# top_schem_rev1.net
KiCad netlist of a schematic drawn in Altium Designer
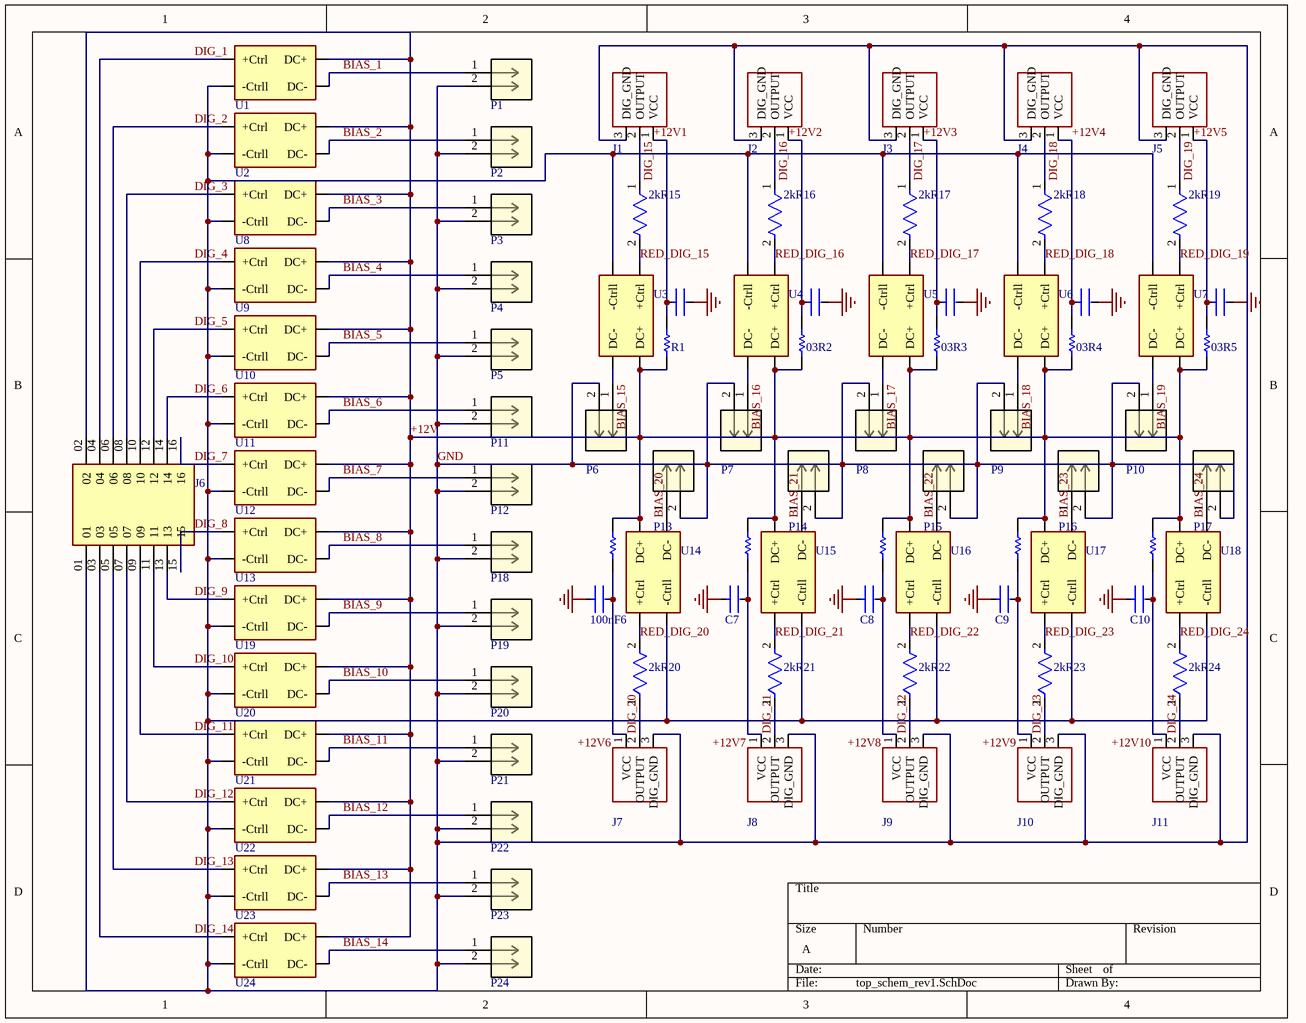
[diagram p0: top_schem_rev1.SchDoc]

(export (version "E")
  (design (tool "Eeschema 10.0.6"))
  (components
    (comp (ref "2kR15")
      (value "CRCW06031K80FKEA")
      (footprint "2kOhm")
      (description "Res Thick Film 0603 1.8K Ohm 1% 1/10W ±100ppm/°C Molded SMD Paper T/R")
      (fields (field (name "MANUFACTURER") "Vishay") (field (name "TOLERANCE") "1%"))
      (libsource (lib "ps_schlib") (part "CRCW06031K80FKEA"))
    )
    (comp (ref "2kR16")
      (value "CRCW06031K80FKEA")
      (footprint "2kOhm")
      (description "Res Thick Film 0603 1.8K Ohm 1% 1/10W ±100ppm/°C Molded SMD Paper T/R")
      (fields (field (name "MANUFACTURER") "Vishay") (field (name "TOLERANCE") "1%"))
      (libsource (lib "ps_schlib") (part "CRCW06031K80FKEA"))
    )
    (comp (ref "2kR17")
      (value "CRCW06031K80FKEA")
      (footprint "2kOhm")
      (description "Res Thick Film 0603 1.8K Ohm 1% 1/10W ±100ppm/°C Molded SMD Paper T/R")
      (fields (field (name "MANUFACTURER") "Vishay") (field (name "TOLERANCE") "1%"))
      (libsource (lib "ps_schlib") (part "CRCW06031K80FKEA"))
    )
    (comp (ref "2kR18")
      (value "CRCW06031K80FKEA")
      (footprint "2kOhm")
      (description "Res Thick Film 0603 1.8K Ohm 1% 1/10W ±100ppm/°C Molded SMD Paper T/R")
      (fields (field (name "MANUFACTURER") "Vishay") (field (name "TOLERANCE") "1%"))
      (libsource (lib "ps_schlib") (part "CRCW06031K80FKEA"))
    )
    (comp (ref "2kR19")
      (value "CRCW06031K80FKEA")
      (footprint "2kOhm")
      (description "Res Thick Film 0603 1.8K Ohm 1% 1/10W ±100ppm/°C Molded SMD Paper T/R")
      (fields (field (name "MANUFACTURER") "Vishay") (field (name "TOLERANCE") "1%"))
      (libsource (lib "ps_schlib") (part "CRCW06031K80FKEA"))
    )
    (comp (ref "2kR20")
      (value "CRCW06031K80FKEA")
      (footprint "2kOhm")
      (description "Res Thick Film 0603 1.8K Ohm 1% 1/10W ±100ppm/°C Molded SMD Paper T/R")
      (fields (field (name "MANUFACTURER") "Vishay") (field (name "TOLERANCE") "1%"))
      (libsource (lib "ps_schlib") (part "CRCW06031K80FKEA"))
    )
    (comp (ref "2kR21")
      (value "CRCW06031K80FKEA")
      (footprint "2kOhm")
      (description "Res Thick Film 0603 1.8K Ohm 1% 1/10W ±100ppm/°C Molded SMD Paper T/R")
      (fields (field (name "MANUFACTURER") "Vishay") (field (name "TOLERANCE") "1%"))
      (libsource (lib "ps_schlib") (part "CRCW06031K80FKEA"))
    )
    (comp (ref "2kR22")
      (value "CRCW06031K80FKEA")
      (footprint "2kOhm")
      (description "Res Thick Film 0603 1.8K Ohm 1% 1/10W ±100ppm/°C Molded SMD Paper T/R")
      (fields (field (name "MANUFACTURER") "Vishay") (field (name "TOLERANCE") "1%"))
      (libsource (lib "ps_schlib") (part "CRCW06031K80FKEA"))
    )
    (comp (ref "2kR23")
      (value "CRCW06031K80FKEA")
      (footprint "2kOhm")
      (description "Res Thick Film 0603 1.8K Ohm 1% 1/10W ±100ppm/°C Molded SMD Paper T/R")
      (fields (field (name "MANUFACTURER") "Vishay") (field (name "TOLERANCE") "1%"))
      (libsource (lib "ps_schlib") (part "CRCW06031K80FKEA"))
    )
    (comp (ref "2kR24")
      (value "CRCW06031K80FKEA")
      (footprint "2kOhm")
      (description "Res Thick Film 0603 1.8K Ohm 1% 1/10W ±100ppm/°C Molded SMD Paper T/R")
      (fields (field (name "MANUFACTURER") "Vishay") (field (name "TOLERANCE") "1%"))
      (libsource (lib "ps_schlib") (part "CRCW06031K80FKEA"))
    )
    (comp (ref "03R2")
      (value "ERJ-2BQJR30X")
      (footprint "03 Ohm")
      (description "RES 0.3 OHM 5% 1/6W 0402")
      (fields (field (name "MANUFACTURER") "Panasonic") (field (name "TOLERANCE") "5%"))
      (libsource (lib "ps_schlib") (part "ERJ-2BQJR30X"))
    )
    (comp (ref "03R3")
      (value "ERJ-2BQJR30X")
      (footprint "03 Ohm")
      (description "RES 0.3 OHM 5% 1/6W 0402")
      (fields (field (name "MANUFACTURER") "Panasonic") (field (name "TOLERANCE") "5%"))
      (libsource (lib "ps_schlib") (part "ERJ-2BQJR30X"))
    )
    (comp (ref "03R4")
      (value "ERJ-2BQJR30X")
      (footprint "03 Ohm")
      (description "RES 0.3 OHM 5% 1/6W 0402")
      (fields (field (name "MANUFACTURER") "Panasonic") (field (name "TOLERANCE") "5%"))
      (libsource (lib "ps_schlib") (part "ERJ-2BQJR30X"))
    )
    (comp (ref "03R5")
      (value "ERJ-2BQJR30X")
      (footprint "03 Ohm")
      (description "RES 0.3 OHM 5% 1/6W 0402")
      (fields (field (name "MANUFACTURER") "Panasonic") (field (name "TOLERANCE") "5%"))
      (libsource (lib "ps_schlib") (part "ERJ-2BQJR30X"))
    )
    (comp (ref "03R7")
      (value "ERJ-2BQJR30X")
      (footprint "03 Ohm")
      (description "RES 0.3 OHM 5% 1/6W 0402")
      (fields (field (name "MANUFACTURER") "Panasonic") (field (name "TOLERANCE") "5%"))
      (libsource (lib "ps_schlib") (part "ERJ-2BQJR30X"))
    )
    (comp (ref "03R8")
      (value "ERJ-2BQJR30X")
      (footprint "03 Ohm")
      (description "RES 0.3 OHM 5% 1/6W 0402")
      (fields (field (name "MANUFACTURER") "Panasonic") (field (name "TOLERANCE") "5%"))
      (libsource (lib "ps_schlib") (part "ERJ-2BQJR30X"))
    )
    (comp (ref "03R9")
      (value "ERJ-2BQJR30X")
      (footprint "03 Ohm")
      (description "RES 0.3 OHM 5% 1/6W 0402")
      (fields (field (name "MANUFACTURER") "Panasonic") (field (name "TOLERANCE") "5%"))
      (libsource (lib "ps_schlib") (part "ERJ-2BQJR30X"))
    )
    (comp (ref "03R10")
      (value "ERJ-2BQJR30X")
      (footprint "03 Ohm")
      (description "RES 0.3 OHM 5% 1/6W 0402")
      (fields (field (name "MANUFACTURER") "Panasonic") (field (name "TOLERANCE") "5%"))
      (libsource (lib "ps_schlib") (part "ERJ-2BQJR30X"))
    )
    (comp (ref "100nF1")
      (value "C0805C104K5RACTU")
      (footprint "100nF")
      (description "Cap Ceramic 0.1uF 50V X7R 10% SMD 2.0 x 1.2 mm 125 C Paper T/R")
      (fields (field (name "MANUFACTURER") "KEMET") (field (name "TOLERANCE") "10%"))
      (libsource (lib "ps_schlib") (part "C0805C104K5RACTU"))
    )
    (comp (ref "100nF6")
      (value "C0805C104K5RACTU")
      (footprint "100nF")
      (description "Cap Ceramic 0.1uF 50V X7R 10% SMD 2.0 x 1.2 mm 125 C Paper T/R")
      (fields (field (name "MANUFACTURER") "KEMET") (field (name "TOLERANCE") "10%"))
      (libsource (lib "ps_schlib") (part "C0805C104K5RACTU"))
    )
    (comp (ref "C2")
      (value "C0805C104K5RACTU")
      (footprint "100nF")
      (description "Cap Ceramic 0.1uF 50V X7R 10% SMD 2.0 x 1.2 mm 125 C Paper T/R")
      (fields (field (name "MANUFACTURER") "KEMET") (field (name "TOLERANCE") "10%"))
      (libsource (lib "ps_schlib") (part "C0805C104K5RACTU"))
    )
    (comp (ref "C3")
      (value "C0805C104K5RACTU")
      (footprint "100nF")
      (description "Cap Ceramic 0.1uF 50V X7R 10% SMD 2.0 x 1.2 mm 125 C Paper T/R")
      (fields (field (name "MANUFACTURER") "KEMET") (field (name "TOLERANCE") "10%"))
      (libsource (lib "ps_schlib") (part "C0805C104K5RACTU"))
    )
    (comp (ref "C4")
      (value "C0805C104K5RACTU")
      (footprint "100nF")
      (description "Cap Ceramic 0.1uF 50V X7R 10% SMD 2.0 x 1.2 mm 125 C Paper T/R")
      (fields (field (name "MANUFACTURER") "KEMET") (field (name "TOLERANCE") "10%"))
      (libsource (lib "ps_schlib") (part "C0805C104K5RACTU"))
    )
    (comp (ref "C5")
      (value "C0805C104K5RACTU")
      (footprint "100nF")
      (description "Cap Ceramic 0.1uF 50V X7R 10% SMD 2.0 x 1.2 mm 125 C Paper T/R")
      (fields (field (name "MANUFACTURER") "KEMET") (field (name "TOLERANCE") "10%"))
      (libsource (lib "ps_schlib") (part "C0805C104K5RACTU"))
    )
    (comp (ref "C7")
      (value "C0805C104K5RACTU")
      (footprint "100nF")
      (description "Cap Ceramic 0.1uF 50V X7R 10% SMD 2.0 x 1.2 mm 125 C Paper T/R")
      (fields (field (name "MANUFACTURER") "KEMET") (field (name "TOLERANCE") "10%"))
      (libsource (lib "ps_schlib") (part "C0805C104K5RACTU"))
    )
    (comp (ref "C8")
      (value "C0805C104K5RACTU")
      (footprint "100nF")
      (description "Cap Ceramic 0.1uF 50V X7R 10% SMD 2.0 x 1.2 mm 125 C Paper T/R")
      (fields (field (name "MANUFACTURER") "KEMET") (field (name "TOLERANCE") "10%"))
      (libsource (lib "ps_schlib") (part "C0805C104K5RACTU"))
    )
    (comp (ref "C9")
      (value "C0805C104K5RACTU")
      (footprint "100nF")
      (description "Cap Ceramic 0.1uF 50V X7R 10% SMD 2.0 x 1.2 mm 125 C Paper T/R")
      (fields (field (name "MANUFACTURER") "KEMET") (field (name "TOLERANCE") "10%"))
      (libsource (lib "ps_schlib") (part "C0805C104K5RACTU"))
    )
    (comp (ref "C10")
      (value "C0805C104K5RACTU")
      (footprint "100nF")
      (description "Cap Ceramic 0.1uF 50V X7R 10% SMD 2.0 x 1.2 mm 125 C Paper T/R")
      (fields (field (name "MANUFACTURER") "KEMET") (field (name "TOLERANCE") "10%"))
      (libsource (lib "ps_schlib") (part "C0805C104K5RACTU"))
    )
    (comp (ref "J1")
      (value "IF-D95T")
      (footprint "IF-D95")
      (description "DETECTOR PHOTOLOGIC TTL/CMOS")
      (fields (field (name "MANUFACTURER") "Industrial Fiber Optics"))
      (libsource (lib "ps_schlib") (part "IF-D95T"))
    )
    (comp (ref "J2")
      (value "IF-D95T")
      (footprint "IF-D95")
      (description "DETECTOR PHOTOLOGIC TTL/CMOS")
      (fields (field (name "MANUFACTURER") "Industrial Fiber Optics"))
      (libsource (lib "ps_schlib") (part "IF-D95T"))
    )
    (comp (ref "J3")
      (value "IF-D95T")
      (footprint "IF-D95")
      (description "DETECTOR PHOTOLOGIC TTL/CMOS")
      (fields (field (name "MANUFACTURER") "Industrial Fiber Optics"))
      (libsource (lib "ps_schlib") (part "IF-D95T"))
    )
    (comp (ref "J4")
      (value "IF-D95T")
      (footprint "IF-D95")
      (description "DETECTOR PHOTOLOGIC TTL/CMOS")
      (fields (field (name "MANUFACTURER") "Industrial Fiber Optics"))
      (libsource (lib "ps_schlib") (part "IF-D95T"))
    )
    (comp (ref "J5")
      (value "IF-D95T")
      (footprint "IF-D95")
      (description "DETECTOR PHOTOLOGIC TTL/CMOS")
      (fields (field (name "MANUFACTURER") "Industrial Fiber Optics"))
      (libsource (lib "ps_schlib") (part "IF-D95T"))
    )
    (comp (ref "J6")
      (value "SSM-108-X-DV")
      (footprint "16 pin header")
      (libsource (lib "ps_schlib") (part "SSM-108-X-DV"))
    )
    (comp (ref "J7")
      (value "IF-D95T")
      (footprint "IF-D95")
      (description "DETECTOR PHOTOLOGIC TTL/CMOS")
      (fields (field (name "MANUFACTURER") "Industrial Fiber Optics"))
      (libsource (lib "ps_schlib") (part "IF-D95T"))
    )
    (comp (ref "J8")
      (value "IF-D95T")
      (footprint "IF-D95")
      (description "DETECTOR PHOTOLOGIC TTL/CMOS")
      (fields (field (name "MANUFACTURER") "Industrial Fiber Optics"))
      (libsource (lib "ps_schlib") (part "IF-D95T"))
    )
    (comp (ref "J9")
      (value "IF-D95T")
      (footprint "IF-D95")
      (description "DETECTOR PHOTOLOGIC TTL/CMOS")
      (fields (field (name "MANUFACTURER") "Industrial Fiber Optics"))
      (libsource (lib "ps_schlib") (part "IF-D95T"))
    )
    (comp (ref "J10")
      (value "IF-D95T")
      (footprint "IF-D95")
      (description "DETECTOR PHOTOLOGIC TTL/CMOS")
      (fields (field (name "MANUFACTURER") "Industrial Fiber Optics"))
      (libsource (lib "ps_schlib") (part "IF-D95T"))
    )
    (comp (ref "J11")
      (value "IF-D95T")
      (footprint "IF-D95")
      (description "DETECTOR PHOTOLOGIC TTL/CMOS")
      (fields (field (name "MANUFACTURER") "Industrial Fiber Optics"))
      (libsource (lib "ps_schlib") (part "IF-D95T"))
    )
    (comp (ref "P1")
      (value "1054311102")
      (footprint "CONN_1054311102_MOL")
      (fields (field (name "MANUFACTURER") "Molex"))
      (libsource (lib "") (part "1054311102_1"))
    )
    (comp (ref "P2")
      (value "1054311102")
      (footprint "CONN_1054311102_MOL")
      (fields (field (name "MANUFACTURER") "Molex"))
      (libsource (lib "") (part "1054311102_1"))
    )
    (comp (ref "P3")
      (value "1054311102")
      (footprint "CONN_1054311102_MOL")
      (fields (field (name "MANUFACTURER") "Molex"))
      (libsource (lib "") (part "1054311102_1"))
    )
    (comp (ref "P4")
      (value "1054311102")
      (footprint "CONN_1054311102_MOL")
      (fields (field (name "MANUFACTURER") "Molex"))
      (libsource (lib "") (part "1054311102_1"))
    )
    (comp (ref "P5")
      (value "1054311102")
      (footprint "CONN_1054311102_MOL")
      (fields (field (name "MANUFACTURER") "Molex"))
      (libsource (lib "") (part "1054311102_1"))
    )
    (comp (ref "P6")
      (value "1054311102")
      (footprint "CONN_1054311102_MOL")
      (fields (field (name "MANUFACTURER") "Molex"))
      (libsource (lib "ps_schlib") (part "1054311102"))
    )
    (comp (ref "P7")
      (value "1054311102")
      (footprint "CONN_1054311102_MOL")
      (fields (field (name "MANUFACTURER") "Molex"))
      (libsource (lib "ps_schlib") (part "1054311102"))
    )
    (comp (ref "P8")
      (value "1054311102")
      (footprint "CONN_1054311102_MOL")
      (fields (field (name "MANUFACTURER") "Molex"))
      (libsource (lib "ps_schlib") (part "1054311102"))
    )
    (comp (ref "P9")
      (value "1054311102")
      (footprint "CONN_1054311102_MOL")
      (fields (field (name "MANUFACTURER") "Molex"))
      (libsource (lib "ps_schlib") (part "1054311102"))
    )
    (comp (ref "P10")
      (value "1054311102")
      (footprint "CONN_1054311102_MOL")
      (fields (field (name "MANUFACTURER") "Molex"))
      (libsource (lib "ps_schlib") (part "1054311102"))
    )
    (comp (ref "P11")
      (value "1054311102")
      (footprint "CONN_1054311102_MOL")
      (fields (field (name "MANUFACTURER") "Molex"))
      (libsource (lib "") (part "1054311102_1"))
    )
    (comp (ref "P12")
      (value "1054311102")
      (footprint "CONN_1054311102_MOL")
      (fields (field (name "MANUFACTURER") "Molex"))
      (libsource (lib "") (part "1054311102_1"))
    )
    (comp (ref "P13")
      (value "1054311102")
      (footprint "CONN_1054311102_MOL")
      (fields (field (name "MANUFACTURER") "Molex"))
      (libsource (lib "") (part "1054311102_2"))
    )
    (comp (ref "P14")
      (value "1054311102")
      (footprint "CONN_1054311102_MOL")
      (fields (field (name "MANUFACTURER") "Molex"))
      (libsource (lib "") (part "1054311102_2"))
    )
    (comp (ref "P15")
      (value "1054311102")
      (footprint "CONN_1054311102_MOL")
      (fields (field (name "MANUFACTURER") "Molex"))
      (libsource (lib "") (part "1054311102_2"))
    )
    (comp (ref "P16")
      (value "1054311102")
      (footprint "CONN_1054311102_MOL")
      (fields (field (name "MANUFACTURER") "Molex"))
      (libsource (lib "") (part "1054311102_2"))
    )
    (comp (ref "P17")
      (value "1054311102")
      (footprint "CONN_1054311102_MOL")
      (fields (field (name "MANUFACTURER") "Molex"))
      (libsource (lib "") (part "1054311102_2"))
    )
    (comp (ref "P18")
      (value "1054311102")
      (footprint "CONN_1054311102_MOL")
      (fields (field (name "MANUFACTURER") "Molex"))
      (libsource (lib "") (part "1054311102_1"))
    )
    (comp (ref "P19")
      (value "1054311102")
      (footprint "CONN_1054311102_MOL")
      (fields (field (name "MANUFACTURER") "Molex"))
      (libsource (lib "") (part "1054311102_1"))
    )
    (comp (ref "P20")
      (value "1054311102")
      (footprint "CONN_1054311102_MOL")
      (fields (field (name "MANUFACTURER") "Molex"))
      (libsource (lib "") (part "1054311102_1"))
    )
    (comp (ref "P21")
      (value "1054311102")
      (footprint "CONN_1054311102_MOL")
      (fields (field (name "MANUFACTURER") "Molex"))
      (libsource (lib "") (part "1054311102_1"))
    )
    (comp (ref "P22")
      (value "1054311102")
      (footprint "CONN_1054311102_MOL")
      (fields (field (name "MANUFACTURER") "Molex"))
      (libsource (lib "") (part "1054311102_1"))
    )
    (comp (ref "P23")
      (value "1054311102")
      (footprint "CONN_1054311102_MOL")
      (fields (field (name "MANUFACTURER") "Molex"))
      (libsource (lib "") (part "1054311102_1"))
    )
    (comp (ref "P24")
      (value "1054311102")
      (footprint "CONN_1054311102_MOL")
      (fields (field (name "MANUFACTURER") "Molex"))
      (libsource (lib "") (part "1054311102_1"))
    )
    (comp (ref "R1")
      (value "ERJ-2BQJR30X")
      (footprint "03 Ohm")
      (description "RES 0.3 OHM 5% 1/6W 0402")
      (fields (field (name "MANUFACTURER") "Panasonic") (field (name "TOLERANCE") "5%"))
      (libsource (lib "ps_schlib") (part "ERJ-2BQJR30X"))
    )
    (comp (ref "R6")
      (value "ERJ-2BQJR30X")
      (footprint "03 Ohm")
      (description "RES 0.3 OHM 5% 1/6W 0402")
      (fields (field (name "MANUFACTURER") "Panasonic") (field (name "TOLERANCE") "5%"))
      (libsource (lib "ps_schlib") (part "ERJ-2BQJR30X"))
    )
    (comp (ref "U1")
      (value "Solid state relay")
      (footprint "CPC1002N")
      (libsource (lib "") (part "CPC1002N_2"))
    )
    (comp (ref "U2")
      (value "Solid state relay")
      (footprint "CPC1002N")
      (libsource (lib "") (part "CPC1002N_2"))
    )
    (comp (ref "U3")
      (value "Solid state relay")
      (footprint "CPC1002N")
      (libsource (lib "ps_schlib") (part "CPC1002N"))
    )
    (comp (ref "U4")
      (value "Solid state relay")
      (footprint "CPC1002N")
      (libsource (lib "ps_schlib") (part "CPC1002N"))
    )
    (comp (ref "U5")
      (value "Solid state relay")
      (footprint "CPC1002N")
      (libsource (lib "ps_schlib") (part "CPC1002N"))
    )
    (comp (ref "U6")
      (value "Solid state relay")
      (footprint "CPC1002N")
      (libsource (lib "ps_schlib") (part "CPC1002N"))
    )
    (comp (ref "U7")
      (value "Solid state relay")
      (footprint "CPC1002N")
      (libsource (lib "ps_schlib") (part "CPC1002N"))
    )
    (comp (ref "U8")
      (value "Solid state relay")
      (footprint "CPC1002N")
      (libsource (lib "") (part "CPC1002N_2"))
    )
    (comp (ref "U9")
      (value "Solid state relay")
      (footprint "CPC1002N")
      (libsource (lib "") (part "CPC1002N_2"))
    )
    (comp (ref "U10")
      (value "Solid state relay")
      (footprint "CPC1002N")
      (libsource (lib "") (part "CPC1002N_2"))
    )
    (comp (ref "U11")
      (value "Solid state relay")
      (footprint "CPC1002N")
      (libsource (lib "") (part "CPC1002N_2"))
    )
    (comp (ref "U12")
      (value "Solid state relay")
      (footprint "CPC1002N")
      (libsource (lib "") (part "CPC1002N_2"))
    )
    (comp (ref "U13")
      (value "Solid state relay")
      (footprint "CPC1002N")
      (libsource (lib "") (part "CPC1002N_2"))
    )
    (comp (ref "U14")
      (value "Solid state relay")
      (footprint "CPC1002N")
      (libsource (lib "") (part "CPC1002N_1"))
    )
    (comp (ref "U15")
      (value "Solid state relay")
      (footprint "CPC1002N")
      (libsource (lib "") (part "CPC1002N_1"))
    )
    (comp (ref "U16")
      (value "Solid state relay")
      (footprint "CPC1002N")
      (libsource (lib "") (part "CPC1002N_1"))
    )
    (comp (ref "U17")
      (value "Solid state relay")
      (footprint "CPC1002N")
      (libsource (lib "") (part "CPC1002N_1"))
    )
    (comp (ref "U18")
      (value "Solid state relay")
      (footprint "CPC1002N")
      (libsource (lib "") (part "CPC1002N_1"))
    )
    (comp (ref "U19")
      (value "Solid state relay")
      (footprint "CPC1002N")
      (libsource (lib "") (part "CPC1002N_2"))
    )
    (comp (ref "U20")
      (value "Solid state relay")
      (footprint "CPC1002N")
      (libsource (lib "") (part "CPC1002N_2"))
    )
    (comp (ref "U21")
      (value "Solid state relay")
      (footprint "CPC1002N")
      (libsource (lib "") (part "CPC1002N_2"))
    )
    (comp (ref "U22")
      (value "Solid state relay")
      (footprint "CPC1002N")
      (libsource (lib "") (part "CPC1002N_2"))
    )
    (comp (ref "U23")
      (value "Solid state relay")
      (footprint "CPC1002N")
      (libsource (lib "") (part "CPC1002N_2"))
    )
    (comp (ref "U24")
      (value "Solid state relay")
      (footprint "CPC1002N")
      (libsource (lib "") (part "CPC1002N_2"))
    )
  )
  (nets
    (net (code "1") (name "/+12V") (class "Default")
      (node (ref "03R10") (pin "2") (pinfunction "2_2") (pintype "passive"))
      (node (ref "03R2") (pin "1") (pinfunction "1_1") (pintype "passive"))
      (node (ref "03R3") (pin "1") (pinfunction "1_1") (pintype "passive"))
      (node (ref "03R4") (pin "1") (pinfunction "1_1") (pintype "passive"))
      (node (ref "03R5") (pin "1") (pinfunction "1_1") (pintype "passive"))
      (node (ref "03R7") (pin "2") (pinfunction "2_2") (pintype "passive"))
      (node (ref "03R8") (pin "2") (pinfunction "2_2") (pintype "passive"))
      (node (ref "03R9") (pin "2") (pinfunction "2_2") (pintype "passive"))
      (node (ref "J6") (pin "02") (pinfunction "02_02") (pintype "passive"))
      (node (ref "R1") (pin "1") (pinfunction "1_1") (pintype "passive"))
      (node (ref "R6") (pin "2") (pinfunction "2_2") (pintype "passive"))
      (node (ref "U1") (pin "4") (pinfunction "DC+_4") (pintype "passive"))
      (node (ref "U10") (pin "4") (pinfunction "DC+_4") (pintype "passive"))
      (node (ref "U11") (pin "4") (pinfunction "DC+_4") (pintype "passive"))
      (node (ref "U12") (pin "4") (pinfunction "DC+_4") (pintype "passive"))
      (node (ref "U13") (pin "4") (pinfunction "DC+_4") (pintype "passive"))
      (node (ref "U14") (pin "4") (pinfunction "DC+_4") (pintype "passive"))
      (node (ref "U15") (pin "4") (pinfunction "DC+_4") (pintype "passive"))
      (node (ref "U16") (pin "4") (pinfunction "DC+_4") (pintype "passive"))
      (node (ref "U17") (pin "4") (pinfunction "DC+_4") (pintype "passive"))
      (node (ref "U18") (pin "4") (pinfunction "DC+_4") (pintype "passive"))
      (node (ref "U19") (pin "4") (pinfunction "DC+_4") (pintype "passive"))
      (node (ref "U2") (pin "4") (pinfunction "DC+_4") (pintype "passive"))
      (node (ref "U20") (pin "4") (pinfunction "DC+_4") (pintype "passive"))
      (node (ref "U21") (pin "4") (pinfunction "DC+_4") (pintype "passive"))
      (node (ref "U22") (pin "4") (pinfunction "DC+_4") (pintype "passive"))
      (node (ref "U23") (pin "4") (pinfunction "DC+_4") (pintype "passive"))
      (node (ref "U24") (pin "4") (pinfunction "DC+_4") (pintype "passive"))
      (node (ref "U3") (pin "4") (pinfunction "DC+_4") (pintype "passive"))
      (node (ref "U4") (pin "4") (pinfunction "DC+_4") (pintype "passive"))
      (node (ref "U5") (pin "4") (pinfunction "DC+_4") (pintype "passive"))
      (node (ref "U6") (pin "4") (pinfunction "DC+_4") (pintype "passive"))
      (node (ref "U7") (pin "4") (pinfunction "DC+_4") (pintype "passive"))
      (node (ref "U8") (pin "4") (pinfunction "DC+_4") (pintype "passive"))
      (node (ref "U9") (pin "4") (pinfunction "DC+_4") (pintype "passive"))
    )
    (net (code "2") (name "/+12V1") (class "Default")
      (node (ref "100nF1") (pin "1") (pinfunction "1_1") (pintype "passive"))
      (node (ref "J1") (pin "1") (pinfunction "VCC_1") (pintype "passive"))
      (node (ref "R1") (pin "2") (pinfunction "2_2") (pintype "passive"))
    )
    (net (code "3") (name "/+12V2") (class "Default")
      (node (ref "03R2") (pin "2") (pinfunction "2_2") (pintype "passive"))
      (node (ref "C2") (pin "1") (pinfunction "1_1") (pintype "passive"))
      (node (ref "J2") (pin "1") (pinfunction "VCC_1") (pintype "passive"))
    )
    (net (code "4") (name "/+12V3") (class "Default")
      (node (ref "03R3") (pin "2") (pinfunction "2_2") (pintype "passive"))
      (node (ref "C3") (pin "1") (pinfunction "1_1") (pintype "passive"))
      (node (ref "J3") (pin "1") (pinfunction "VCC_1") (pintype "passive"))
    )
    (net (code "5") (name "/+12V4") (class "Default")
      (node (ref "03R4") (pin "2") (pinfunction "2_2") (pintype "passive"))
      (node (ref "C4") (pin "1") (pinfunction "1_1") (pintype "passive"))
      (node (ref "J4") (pin "1") (pinfunction "VCC_1") (pintype "passive"))
    )
    (net (code "6") (name "/+12V5") (class "Default")
      (node (ref "03R5") (pin "2") (pinfunction "2_2") (pintype "passive"))
      (node (ref "C5") (pin "1") (pinfunction "1_1") (pintype "passive"))
      (node (ref "J5") (pin "1") (pinfunction "VCC_1") (pintype "passive"))
    )
    (net (code "7") (name "/+12V6") (class "Default")
      (node (ref "100nF6") (pin "2") (pinfunction "2_2") (pintype "passive"))
      (node (ref "J7") (pin "1") (pinfunction "VCC_1") (pintype "passive"))
      (node (ref "R6") (pin "1") (pinfunction "1_1") (pintype "passive"))
    )
    (net (code "8") (name "/+12V7") (class "Default")
      (node (ref "03R7") (pin "1") (pinfunction "1_1") (pintype "passive"))
      (node (ref "C7") (pin "2") (pinfunction "2_2") (pintype "passive"))
      (node (ref "J8") (pin "1") (pinfunction "VCC_1") (pintype "passive"))
    )
    (net (code "9") (name "/+12V8") (class "Default")
      (node (ref "03R8") (pin "1") (pinfunction "1_1") (pintype "passive"))
      (node (ref "C8") (pin "2") (pinfunction "2_2") (pintype "passive"))
      (node (ref "J9") (pin "1") (pinfunction "VCC_1") (pintype "passive"))
    )
    (net (code "10") (name "/+12V9") (class "Default")
      (node (ref "03R9") (pin "1") (pinfunction "1_1") (pintype "passive"))
      (node (ref "C9") (pin "2") (pinfunction "2_2") (pintype "passive"))
      (node (ref "J10") (pin "1") (pinfunction "VCC_1") (pintype "passive"))
    )
    (net (code "11") (name "/+12V10") (class "Default")
      (node (ref "03R10") (pin "1") (pinfunction "1_1") (pintype "passive"))
      (node (ref "C10") (pin "2") (pinfunction "2_2") (pintype "passive"))
      (node (ref "J11") (pin "1") (pinfunction "VCC_1") (pintype "passive"))
    )
    (net (code "12") (name "/BIAS_1") (class "Default")
      (node (ref "P1") (pin "1") (pinfunction "1_1") (pintype "passive"))
      (node (ref "U1") (pin "3") (pinfunction "DC-_3") (pintype "passive"))
    )
    (net (code "13") (name "/BIAS_2") (class "Default")
      (node (ref "P2") (pin "1") (pinfunction "1_1") (pintype "passive"))
      (node (ref "U2") (pin "3") (pinfunction "DC-_3") (pintype "passive"))
    )
    (net (code "14") (name "/BIAS_3") (class "Default")
      (node (ref "P3") (pin "1") (pinfunction "1_1") (pintype "passive"))
      (node (ref "U8") (pin "3") (pinfunction "DC-_3") (pintype "passive"))
    )
    (net (code "15") (name "/BIAS_4") (class "Default")
      (node (ref "P4") (pin "1") (pinfunction "1_1") (pintype "passive"))
      (node (ref "U9") (pin "3") (pinfunction "DC-_3") (pintype "passive"))
    )
    (net (code "16") (name "/BIAS_5") (class "Default")
      (node (ref "P5") (pin "1") (pinfunction "1_1") (pintype "passive"))
      (node (ref "U10") (pin "3") (pinfunction "DC-_3") (pintype "passive"))
    )
    (net (code "17") (name "/BIAS_6") (class "Default")
      (node (ref "P11") (pin "1") (pinfunction "1_1") (pintype "passive"))
      (node (ref "U11") (pin "3") (pinfunction "DC-_3") (pintype "passive"))
    )
    (net (code "18") (name "/BIAS_7") (class "Default")
      (node (ref "P12") (pin "1") (pinfunction "1_1") (pintype "passive"))
      (node (ref "U12") (pin "3") (pinfunction "DC-_3") (pintype "passive"))
    )
    (net (code "19") (name "/BIAS_8") (class "Default")
      (node (ref "P18") (pin "1") (pinfunction "1_1") (pintype "passive"))
      (node (ref "U13") (pin "3") (pinfunction "DC-_3") (pintype "passive"))
    )
    (net (code "20") (name "/BIAS_9") (class "Default")
      (node (ref "P19") (pin "1") (pinfunction "1_1") (pintype "passive"))
      (node (ref "U19") (pin "3") (pinfunction "DC-_3") (pintype "passive"))
    )
    (net (code "21") (name "/BIAS_10") (class "Default")
      (node (ref "P20") (pin "1") (pinfunction "1_1") (pintype "passive"))
      (node (ref "U20") (pin "3") (pinfunction "DC-_3") (pintype "passive"))
    )
    (net (code "22") (name "/BIAS_11") (class "Default")
      (node (ref "P21") (pin "1") (pinfunction "1_1") (pintype "passive"))
      (node (ref "U21") (pin "3") (pinfunction "DC-_3") (pintype "passive"))
    )
    (net (code "23") (name "/BIAS_12") (class "Default")
      (node (ref "P22") (pin "1") (pinfunction "1_1") (pintype "passive"))
      (node (ref "U22") (pin "3") (pinfunction "DC-_3") (pintype "passive"))
    )
    (net (code "24") (name "/BIAS_13") (class "Default")
      (node (ref "P23") (pin "1") (pinfunction "1_1") (pintype "passive"))
      (node (ref "U23") (pin "3") (pinfunction "DC-_3") (pintype "passive"))
    )
    (net (code "25") (name "/BIAS_14") (class "Default")
      (node (ref "P24") (pin "1") (pinfunction "1_1") (pintype "passive"))
      (node (ref "U24") (pin "3") (pinfunction "DC-_3") (pintype "passive"))
    )
    (net (code "26") (name "/BIAS_15") (class "Default")
      (node (ref "P6") (pin "1") (pinfunction "1_1") (pintype "passive"))
      (node (ref "U3") (pin "3") (pinfunction "DC-_3") (pintype "passive"))
    )
    (net (code "27") (name "/BIAS_16") (class "Default")
      (node (ref "P7") (pin "1") (pinfunction "1_1") (pintype "passive"))
      (node (ref "U4") (pin "3") (pinfunction "DC-_3") (pintype "passive"))
    )
    (net (code "28") (name "/BIAS_17") (class "Default")
      (node (ref "P8") (pin "1") (pinfunction "1_1") (pintype "passive"))
      (node (ref "U5") (pin "3") (pinfunction "DC-_3") (pintype "passive"))
    )
    (net (code "29") (name "/BIAS_18") (class "Default")
      (node (ref "P9") (pin "1") (pinfunction "1_1") (pintype "passive"))
      (node (ref "U6") (pin "3") (pinfunction "DC-_3") (pintype "passive"))
    )
    (net (code "30") (name "/BIAS_19") (class "Default")
      (node (ref "P10") (pin "1") (pinfunction "1_1") (pintype "passive"))
      (node (ref "U7") (pin "3") (pinfunction "DC-_3") (pintype "passive"))
    )
    (net (code "31") (name "/BIAS_20") (class "Default")
      (node (ref "P13") (pin "1") (pinfunction "1_1") (pintype "passive"))
      (node (ref "U14") (pin "3") (pinfunction "DC-_3") (pintype "passive"))
    )
    (net (code "32") (name "/BIAS_21") (class "Default")
      (node (ref "P14") (pin "1") (pinfunction "1_1") (pintype "passive"))
      (node (ref "U15") (pin "3") (pinfunction "DC-_3") (pintype "passive"))
    )
    (net (code "33") (name "/BIAS_22") (class "Default")
      (node (ref "P15") (pin "1") (pinfunction "1_1") (pintype "passive"))
      (node (ref "U16") (pin "3") (pinfunction "DC-_3") (pintype "passive"))
    )
    (net (code "34") (name "/BIAS_23") (class "Default")
      (node (ref "P16") (pin "1") (pinfunction "1_1") (pintype "passive"))
      (node (ref "U17") (pin "3") (pinfunction "DC-_3") (pintype "passive"))
    )
    (net (code "35") (name "/BIAS_24") (class "Default")
      (node (ref "P17") (pin "1") (pinfunction "1_1") (pintype "passive"))
      (node (ref "U18") (pin "3") (pinfunction "DC-_3") (pintype "passive"))
    )
    (net (code "36") (name "/DIG_1") (class "Default")
      (node (ref "J6") (pin "04") (pinfunction "04_04") (pintype "passive"))
      (node (ref "U1") (pin "1") (pinfunction "+Ctrl_1") (pintype "passive"))
    )
    (net (code "37") (name "/DIG_2") (class "Default")
      (node (ref "J6") (pin "06") (pinfunction "06_06") (pintype "passive"))
      (node (ref "U2") (pin "1") (pinfunction "+Ctrl_1") (pintype "passive"))
    )
    (net (code "38") (name "/DIG_3") (class "Default")
      (node (ref "J6") (pin "08") (pinfunction "08_08") (pintype "passive"))
      (node (ref "U8") (pin "1") (pinfunction "+Ctrl_1") (pintype "passive"))
    )
    (net (code "39") (name "/DIG_4") (class "Default")
      (node (ref "J6") (pin "10") (pinfunction "10_10") (pintype "passive"))
      (node (ref "U9") (pin "1") (pinfunction "+Ctrl_1") (pintype "passive"))
    )
    (net (code "40") (name "/DIG_5") (class "Default")
      (node (ref "J6") (pin "12") (pinfunction "12_12") (pintype "passive"))
      (node (ref "U10") (pin "1") (pinfunction "+Ctrl_1") (pintype "passive"))
    )
    (net (code "41") (name "/DIG_6") (class "Default")
      (node (ref "J6") (pin "14") (pinfunction "14_14") (pintype "passive"))
      (node (ref "U11") (pin "1") (pinfunction "+Ctrl_1") (pintype "passive"))
    )
    (net (code "42") (name "/DIG_7") (class "Default")
      (node (ref "J6") (pin "16") (pinfunction "16_16") (pintype "passive"))
      (node (ref "U12") (pin "1") (pinfunction "+Ctrl_1") (pintype "passive"))
    )
    (net (code "43") (name "/DIG_8") (class "Default")
      (node (ref "J6") (pin "15") (pinfunction "15_15") (pintype "passive"))
      (node (ref "U13") (pin "1") (pinfunction "+Ctrl_1") (pintype "passive"))
    )
    (net (code "44") (name "/DIG_9") (class "Default")
      (node (ref "J6") (pin "13") (pinfunction "13_13") (pintype "passive"))
      (node (ref "U19") (pin "1") (pinfunction "+Ctrl_1") (pintype "passive"))
    )
    (net (code "45") (name "/DIG_10") (class "Default")
      (node (ref "J6") (pin "11") (pinfunction "11_11") (pintype "passive"))
      (node (ref "U20") (pin "1") (pinfunction "+Ctrl_1") (pintype "passive"))
    )
    (net (code "46") (name "/DIG_11") (class "Default")
      (node (ref "J6") (pin "09") (pinfunction "09_09") (pintype "passive"))
      (node (ref "U21") (pin "1") (pinfunction "+Ctrl_1") (pintype "passive"))
    )
    (net (code "47") (name "/DIG_12") (class "Default")
      (node (ref "J6") (pin "07") (pinfunction "07_07") (pintype "passive"))
      (node (ref "U22") (pin "1") (pinfunction "+Ctrl_1") (pintype "passive"))
    )
    (net (code "48") (name "/DIG_13") (class "Default")
      (node (ref "J6") (pin "05") (pinfunction "05_05") (pintype "passive"))
      (node (ref "U23") (pin "1") (pinfunction "+Ctrl_1") (pintype "passive"))
    )
    (net (code "49") (name "/DIG_14") (class "Default")
      (node (ref "J6") (pin "03") (pinfunction "03_03") (pintype "passive"))
      (node (ref "U24") (pin "1") (pinfunction "+Ctrl_1") (pintype "passive"))
    )
    (net (code "50") (name "/DIG_15") (class "Default")
      (node (ref "2kR15") (pin "1") (pinfunction "1_1") (pintype "passive"))
      (node (ref "J1") (pin "2") (pinfunction "OUTPUT_2") (pintype "passive"))
    )
    (net (code "51") (name "/DIG_16") (class "Default")
      (node (ref "2kR16") (pin "1") (pinfunction "1_1") (pintype "passive"))
      (node (ref "J2") (pin "2") (pinfunction "OUTPUT_2") (pintype "passive"))
    )
    (net (code "52") (name "/DIG_17") (class "Default")
      (node (ref "2kR17") (pin "1") (pinfunction "1_1") (pintype "passive"))
      (node (ref "J3") (pin "2") (pinfunction "OUTPUT_2") (pintype "passive"))
    )
    (net (code "53") (name "/DIG_18") (class "Default")
      (node (ref "2kR18") (pin "1") (pinfunction "1_1") (pintype "passive"))
      (node (ref "J4") (pin "2") (pinfunction "OUTPUT_2") (pintype "passive"))
    )
    (net (code "54") (name "/DIG_19") (class "Default")
      (node (ref "2kR19") (pin "1") (pinfunction "1_1") (pintype "passive"))
      (node (ref "J5") (pin "2") (pinfunction "OUTPUT_2") (pintype "passive"))
    )
    (net (code "55") (name "/DIG_20") (class "Default")
      (node (ref "2kR20") (pin "1") (pinfunction "1_1") (pintype "passive"))
      (node (ref "J7") (pin "2") (pinfunction "OUTPUT_2") (pintype "passive"))
    )
    (net (code "56") (name "/DIG_21") (class "Default")
      (node (ref "2kR21") (pin "1") (pinfunction "1_1") (pintype "passive"))
      (node (ref "J8") (pin "2") (pinfunction "OUTPUT_2") (pintype "passive"))
    )
    (net (code "57") (name "/DIG_22") (class "Default")
      (node (ref "2kR22") (pin "1") (pinfunction "1_1") (pintype "passive"))
      (node (ref "J9") (pin "2") (pinfunction "OUTPUT_2") (pintype "passive"))
    )
    (net (code "58") (name "/DIG_23") (class "Default")
      (node (ref "2kR23") (pin "1") (pinfunction "1_1") (pintype "passive"))
      (node (ref "J10") (pin "2") (pinfunction "OUTPUT_2") (pintype "passive"))
    )
    (net (code "59") (name "/DIG_24") (class "Default")
      (node (ref "2kR24") (pin "1") (pinfunction "1_1") (pintype "passive"))
      (node (ref "J11") (pin "2") (pinfunction "OUTPUT_2") (pintype "passive"))
    )
    (net (code "60") (name "/RED_DIG_15") (class "Default")
      (node (ref "2kR15") (pin "2") (pinfunction "2_2") (pintype "passive"))
      (node (ref "U3") (pin "1") (pinfunction "+Ctrl_1") (pintype "passive"))
    )
    (net (code "61") (name "/RED_DIG_16") (class "Default")
      (node (ref "2kR16") (pin "2") (pinfunction "2_2") (pintype "passive"))
      (node (ref "U4") (pin "1") (pinfunction "+Ctrl_1") (pintype "passive"))
    )
    (net (code "62") (name "/RED_DIG_17") (class "Default")
      (node (ref "2kR17") (pin "2") (pinfunction "2_2") (pintype "passive"))
      (node (ref "U5") (pin "1") (pinfunction "+Ctrl_1") (pintype "passive"))
    )
    (net (code "63") (name "/RED_DIG_18") (class "Default")
      (node (ref "2kR18") (pin "2") (pinfunction "2_2") (pintype "passive"))
      (node (ref "U6") (pin "1") (pinfunction "+Ctrl_1") (pintype "passive"))
    )
    (net (code "64") (name "/RED_DIG_19") (class "Default")
      (node (ref "2kR19") (pin "2") (pinfunction "2_2") (pintype "passive"))
      (node (ref "U7") (pin "1") (pinfunction "+Ctrl_1") (pintype "passive"))
    )
    (net (code "65") (name "/RED_DIG_20") (class "Default")
      (node (ref "2kR20") (pin "2") (pinfunction "2_2") (pintype "passive"))
      (node (ref "U14") (pin "1") (pinfunction "+Ctrl_1") (pintype "passive"))
    )
    (net (code "66") (name "/RED_DIG_21") (class "Default")
      (node (ref "2kR21") (pin "2") (pinfunction "2_2") (pintype "passive"))
      (node (ref "U15") (pin "1") (pinfunction "+Ctrl_1") (pintype "passive"))
    )
    (net (code "67") (name "/RED_DIG_22") (class "Default")
      (node (ref "2kR22") (pin "2") (pinfunction "2_2") (pintype "passive"))
      (node (ref "U16") (pin "1") (pinfunction "+Ctrl_1") (pintype "passive"))
    )
    (net (code "68") (name "/RED_DIG_23") (class "Default")
      (node (ref "2kR23") (pin "2") (pinfunction "2_2") (pintype "passive"))
      (node (ref "U17") (pin "1") (pinfunction "+Ctrl_1") (pintype "passive"))
    )
    (net (code "69") (name "/RED_DIG_24") (class "Default")
      (node (ref "2kR24") (pin "2") (pinfunction "2_2") (pintype "passive"))
      (node (ref "U18") (pin "1") (pinfunction "+Ctrl_1") (pintype "passive"))
    )
    (net (code "70") (name "GND") (class "Default")
      (node (ref "100nF1") (pin "2") (pinfunction "2_2") (pintype "passive"))
      (node (ref "100nF6") (pin "1") (pinfunction "1_1") (pintype "passive"))
      (node (ref "C10") (pin "1") (pinfunction "1_1") (pintype "passive"))
      (node (ref "C2") (pin "2") (pinfunction "2_2") (pintype "passive"))
      (node (ref "C3") (pin "2") (pinfunction "2_2") (pintype "passive"))
      (node (ref "C4") (pin "2") (pinfunction "2_2") (pintype "passive"))
      (node (ref "C5") (pin "2") (pinfunction "2_2") (pintype "passive"))
      (node (ref "C7") (pin "1") (pinfunction "1_1") (pintype "passive"))
      (node (ref "C8") (pin "1") (pinfunction "1_1") (pintype "passive"))
      (node (ref "C9") (pin "1") (pinfunction "1_1") (pintype "passive"))
      (node (ref "J1") (pin "3") (pinfunction "DIG_GND_3") (pintype "passive"))
      (node (ref "J10") (pin "3") (pinfunction "DIG_GND_3") (pintype "passive"))
      (node (ref "J11") (pin "3") (pinfunction "DIG_GND_3") (pintype "passive"))
      (node (ref "J2") (pin "3") (pinfunction "DIG_GND_3") (pintype "passive"))
      (node (ref "J3") (pin "3") (pinfunction "DIG_GND_3") (pintype "passive"))
      (node (ref "J4") (pin "3") (pinfunction "DIG_GND_3") (pintype "passive"))
      (node (ref "J5") (pin "3") (pinfunction "DIG_GND_3") (pintype "passive"))
      (node (ref "J6") (pin "01") (pinfunction "01_01") (pintype "passive"))
      (node (ref "J7") (pin "3") (pinfunction "DIG_GND_3") (pintype "passive"))
      (node (ref "J8") (pin "3") (pinfunction "DIG_GND_3") (pintype "passive"))
      (node (ref "J9") (pin "3") (pinfunction "DIG_GND_3") (pintype "passive"))
      (node (ref "P1") (pin "2") (pinfunction "2_2") (pintype "passive"))
      (node (ref "P10") (pin "2") (pinfunction "2_2") (pintype "passive"))
      (node (ref "P11") (pin "2") (pinfunction "2_2") (pintype "passive"))
      (node (ref "P12") (pin "2") (pinfunction "2_2") (pintype "passive"))
      (node (ref "P13") (pin "2") (pinfunction "2_2") (pintype "passive"))
      (node (ref "P14") (pin "2") (pinfunction "2_2") (pintype "passive"))
      (node (ref "P15") (pin "2") (pinfunction "2_2") (pintype "passive"))
      (node (ref "P16") (pin "2") (pinfunction "2_2") (pintype "passive"))
      (node (ref "P17") (pin "2") (pinfunction "2_2") (pintype "passive"))
      (node (ref "P18") (pin "2") (pinfunction "2_2") (pintype "passive"))
      (node (ref "P19") (pin "2") (pinfunction "2_2") (pintype "passive"))
      (node (ref "P2") (pin "2") (pinfunction "2_2") (pintype "passive"))
      (node (ref "P20") (pin "2") (pinfunction "2_2") (pintype "passive"))
      (node (ref "P21") (pin "2") (pinfunction "2_2") (pintype "passive"))
      (node (ref "P22") (pin "2") (pinfunction "2_2") (pintype "passive"))
      (node (ref "P23") (pin "2") (pinfunction "2_2") (pintype "passive"))
      (node (ref "P24") (pin "2") (pinfunction "2_2") (pintype "passive"))
      (node (ref "P3") (pin "2") (pinfunction "2_2") (pintype "passive"))
      (node (ref "P4") (pin "2") (pinfunction "2_2") (pintype "passive"))
      (node (ref "P5") (pin "2") (pinfunction "2_2") (pintype "passive"))
      (node (ref "P6") (pin "2") (pinfunction "2_2") (pintype "passive"))
      (node (ref "P7") (pin "2") (pinfunction "2_2") (pintype "passive"))
      (node (ref "P8") (pin "2") (pinfunction "2_2") (pintype "passive"))
      (node (ref "P9") (pin "2") (pinfunction "2_2") (pintype "passive"))
      (node (ref "U1") (pin "2") (pinfunction "-Ctrll_2") (pintype "passive"))
      (node (ref "U10") (pin "2") (pinfunction "-Ctrll_2") (pintype "passive"))
      (node (ref "U11") (pin "2") (pinfunction "-Ctrll_2") (pintype "passive"))
      (node (ref "U12") (pin "2") (pinfunction "-Ctrll_2") (pintype "passive"))
      (node (ref "U13") (pin "2") (pinfunction "-Ctrll_2") (pintype "passive"))
      (node (ref "U14") (pin "2") (pinfunction "-Ctrll_2") (pintype "passive"))
      (node (ref "U15") (pin "2") (pinfunction "-Ctrll_2") (pintype "passive"))
      (node (ref "U16") (pin "2") (pinfunction "-Ctrll_2") (pintype "passive"))
      (node (ref "U17") (pin "2") (pinfunction "-Ctrll_2") (pintype "passive"))
      (node (ref "U18") (pin "2") (pinfunction "-Ctrll_2") (pintype "passive"))
      (node (ref "U19") (pin "2") (pinfunction "-Ctrll_2") (pintype "passive"))
      (node (ref "U2") (pin "2") (pinfunction "-Ctrll_2") (pintype "passive"))
      (node (ref "U20") (pin "2") (pinfunction "-Ctrll_2") (pintype "passive"))
      (node (ref "U21") (pin "2") (pinfunction "-Ctrll_2") (pintype "passive"))
      (node (ref "U22") (pin "2") (pinfunction "-Ctrll_2") (pintype "passive"))
      (node (ref "U23") (pin "2") (pinfunction "-Ctrll_2") (pintype "passive"))
      (node (ref "U24") (pin "2") (pinfunction "-Ctrll_2") (pintype "passive"))
      (node (ref "U3") (pin "2") (pinfunction "-Ctrll_2") (pintype "passive"))
      (node (ref "U4") (pin "2") (pinfunction "-Ctrll_2") (pintype "passive"))
      (node (ref "U5") (pin "2") (pinfunction "-Ctrll_2") (pintype "passive"))
      (node (ref "U6") (pin "2") (pinfunction "-Ctrll_2") (pintype "passive"))
      (node (ref "U7") (pin "2") (pinfunction "-Ctrll_2") (pintype "passive"))
      (node (ref "U8") (pin "2") (pinfunction "-Ctrll_2") (pintype "passive"))
      (node (ref "U9") (pin "2") (pinfunction "-Ctrll_2") (pintype "passive"))
    )
  )
)
